# SCH_usb-eneko_2025-04-03.net
KiCad netlist of a schematic drawn in EasyEDA
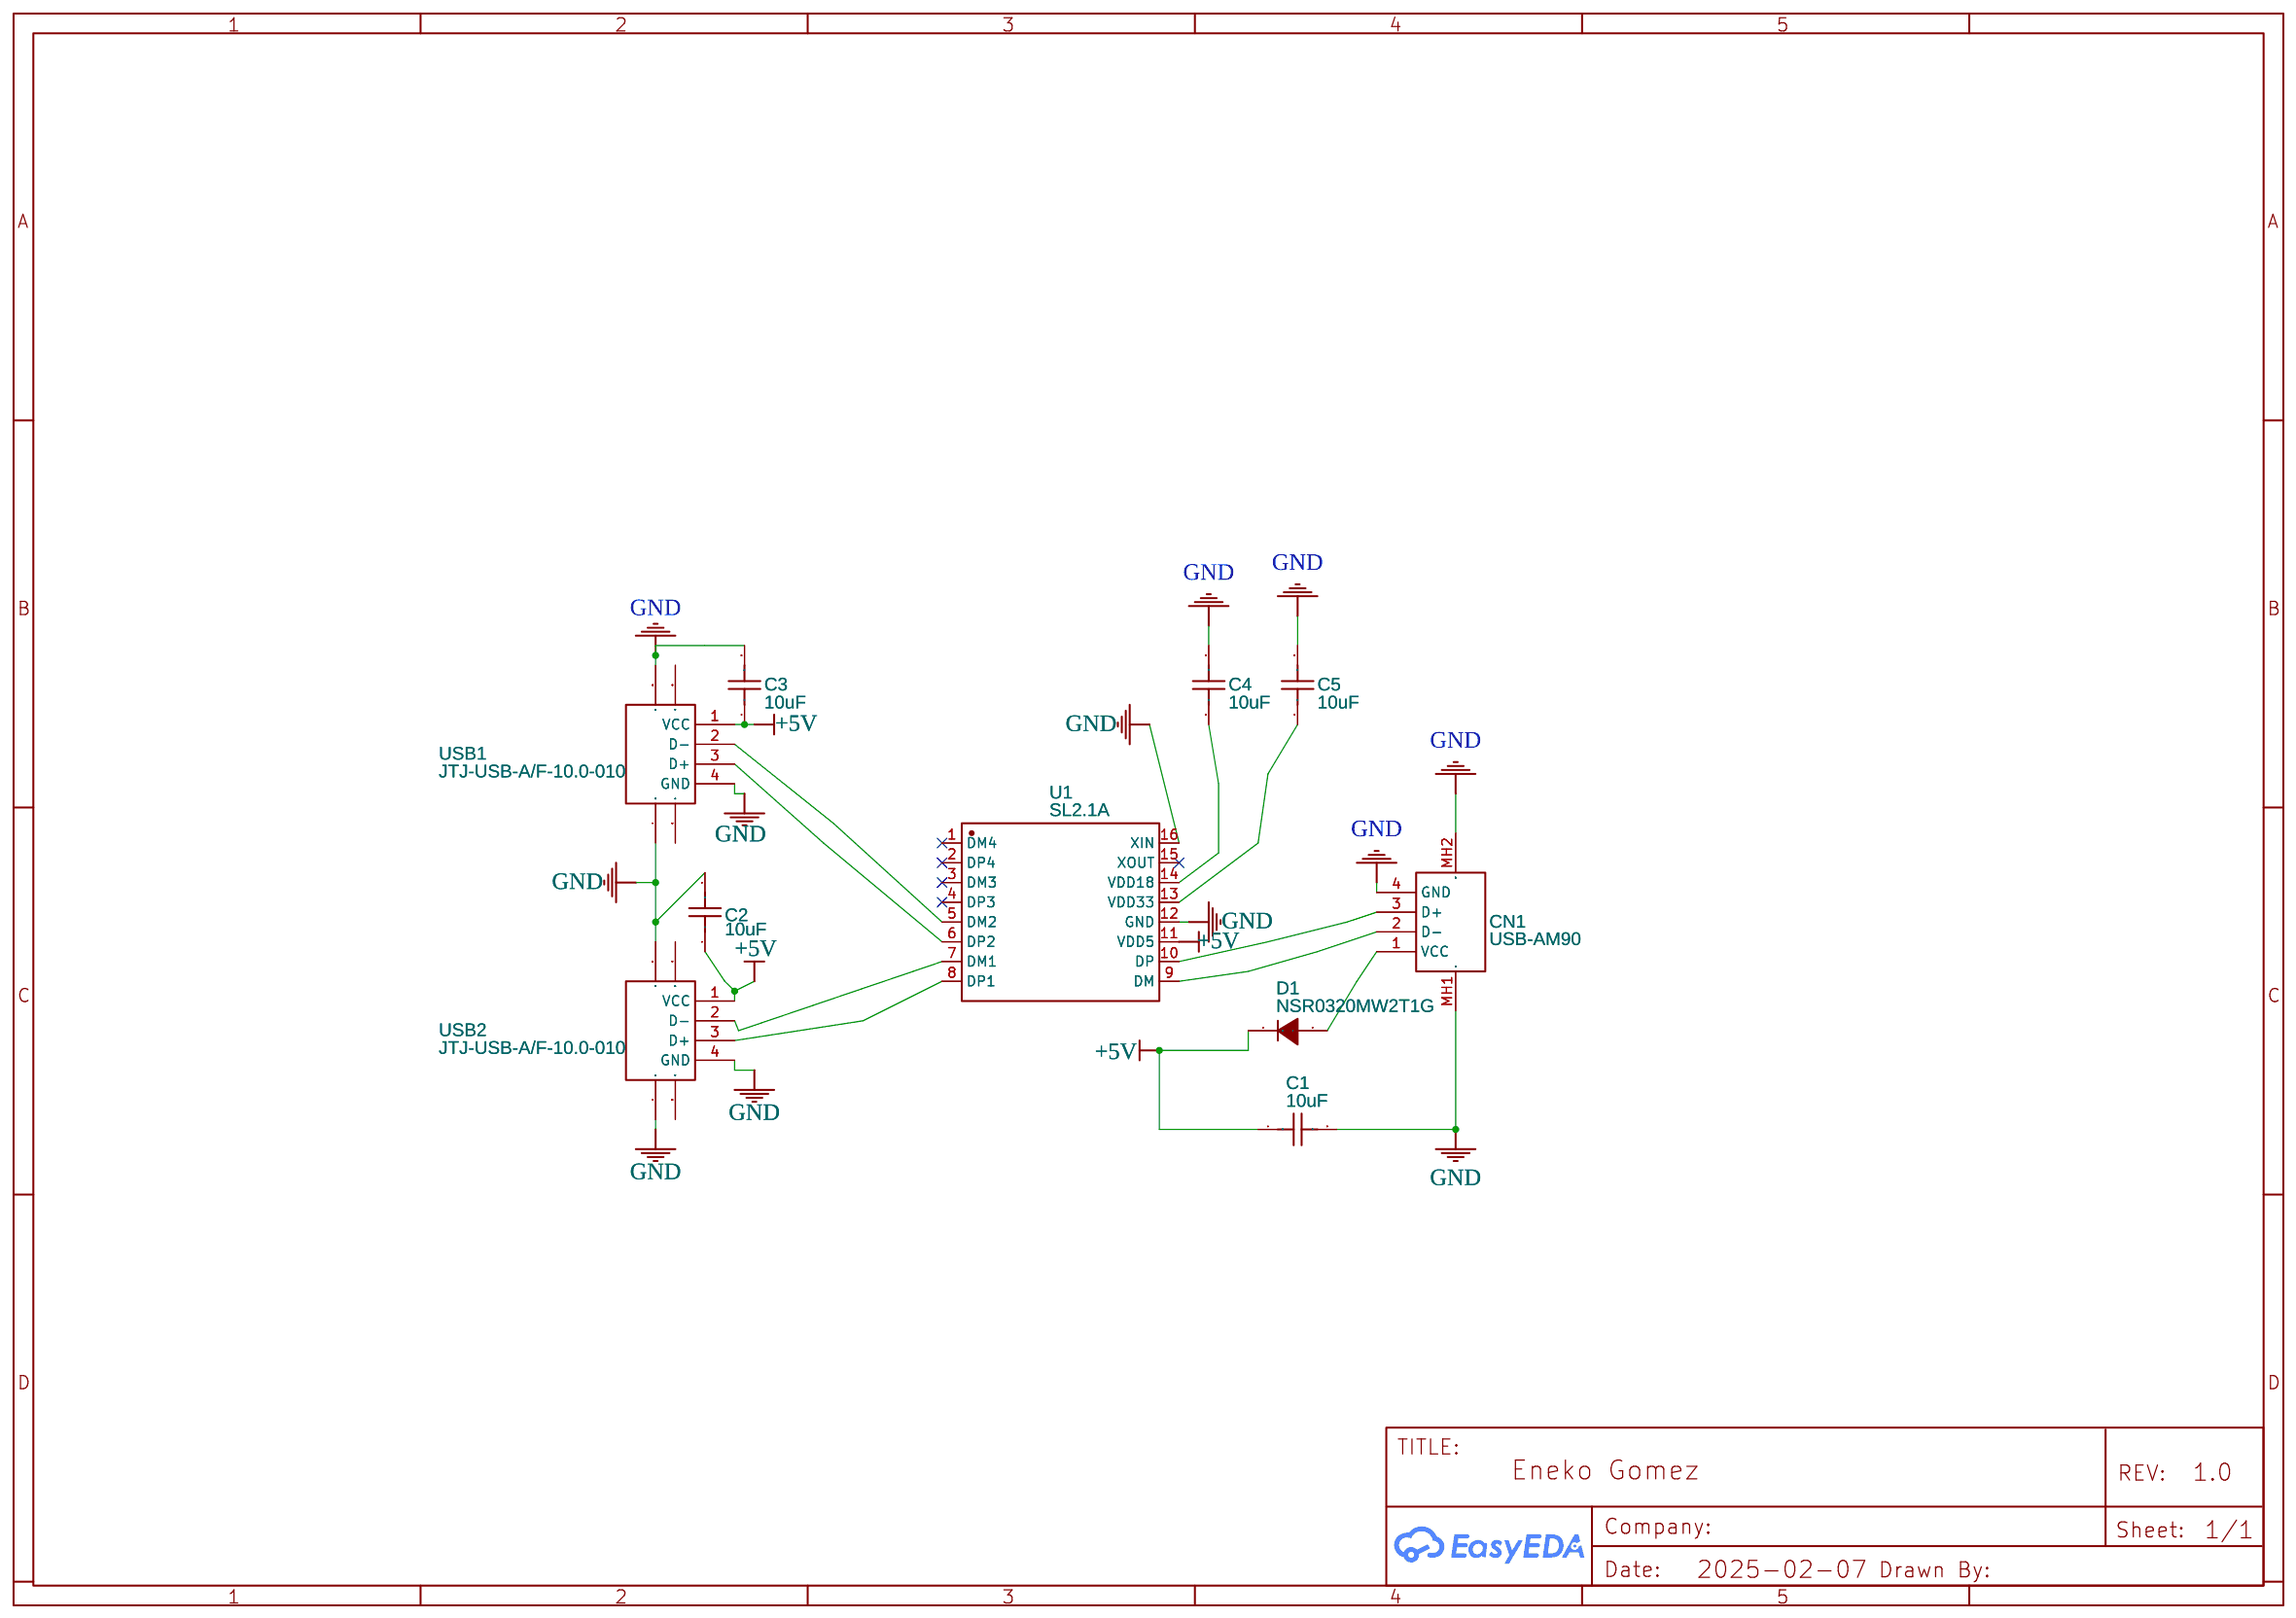
[diagram p0: schematic sheet]

(export (version "E")
  (design (tool "Eeschema 10.0.6"))
  (components
    (comp (ref "C1")
      (value "10uF")
      (fields
        (field (name "Manufacturer Part") "CL10A106KP8NNNC")
        (field (name "Manufacturer") "SAMSUNG(三星)")
      )
      (libsource (lib "") (part "CL10A106KP8NNNC_1"))
    )
    (comp (ref "C2")
      (value "10uF")
      (fields
        (field (name "Manufacturer Part") "CL10A106KP8NNNC")
        (field (name "Manufacturer") "SAMSUNG(三星)")
      )
      (libsource (lib "") (part "CL10A106KP8NNNC"))
    )
    (comp (ref "C3")
      (value "10uF")
      (fields
        (field (name "Manufacturer Part") "CL10A106KP8NNNC")
        (field (name "Manufacturer") "SAMSUNG(三星)")
      )
      (libsource (lib "") (part "CL10A106KP8NNNC"))
    )
    (comp (ref "C4")
      (value "10uF")
      (fields
        (field (name "Manufacturer Part") "CL10A106KP8NNNC")
        (field (name "Manufacturer") "SAMSUNG(三星)")
      )
      (libsource (lib "") (part "CL10A106KP8NNNC"))
    )
    (comp (ref "C5")
      (value "10uF")
      (fields
        (field (name "Manufacturer Part") "CL10A106KP8NNNC")
        (field (name "Manufacturer") "SAMSUNG(三星)")
      )
      (libsource (lib "") (part "CL10A106KP8NNNC"))
    )
    (comp (ref "CN1")
      (value "USB-AM90")
      (fields (field (name "Manufacturer") "ValuePro"))
      (libsource (lib "") (part "USB-AM90"))
    )
    (comp (ref "D1")
      (value "NSR0320MW2T1G")
      (fields (field (name "Manufacturer") "onsemi(安森美)"))
      (libsource (lib "") (part "NSR0320MW2T1G"))
    )
    (comp (ref "U1")
      (value "SL2.1A")
      (fields (field (name "Manufacturer") "CoreChips(和芯润德)"))
      (libsource (lib "") (part "SL2.1A"))
    )
    (comp (ref "USB1")
      (value "JTJ-USB-A/F-10.0-010")
      (fields (field (name "Manufacturer Part") "908-371A1011D10100") (field (name "Manufacturer") "精拓金"))
      (libsource (lib "") (part "JTJ-USB-A/F-10.0-010"))
    )
    (comp (ref "USB2")
      (value "JTJ-USB-A/F-10.0-010")
      (fields (field (name "Manufacturer Part") "908-371A1011D10100") (field (name "Manufacturer") "精拓金"))
      (libsource (lib "") (part "JTJ-USB-A/F-10.0-010"))
    )
  )
  (nets
    (net (code "1") (name "+5V") (class "Default")
      (node (ref "C1") (pin "1") (pinfunction "1_1") (pintype "unspecified"))
      (node (ref "C2") (pin "1") (pinfunction "1_1") (pintype "unspecified"))
      (node (ref "C3") (pin "1") (pinfunction "1_1") (pintype "unspecified"))
      (node (ref "D1") (pin "1") (pinfunction "C_1") (pintype "unspecified"))
      (node (ref "U1") (pin "11") (pinfunction "VDD5_11") (pintype "unspecified"))
      (node (ref "USB1") (pin "1") (pinfunction "VCC_1") (pintype "input"))
      (node (ref "USB2") (pin "1") (pinfunction "VCC_1") (pintype "input"))
    )
    (net (code "2") (name "GND") (class "Default")
      (node (ref "C1") (pin "2") (pinfunction "2_2") (pintype "unspecified"))
      (node (ref "C2") (pin "2") (pinfunction "2_2") (pintype "unspecified"))
      (node (ref "C3") (pin "2") (pinfunction "2_2") (pintype "unspecified"))
      (node (ref "C4") (pin "2") (pinfunction "2_2") (pintype "unspecified"))
      (node (ref "C5") (pin "2") (pinfunction "2_2") (pintype "unspecified"))
      (node (ref "CN1") (pin "4") (pinfunction "GND_4") (pintype "input"))
      (node (ref "CN1") (pin "MH1") (pinfunction "MH1_MH1") (pintype "unspecified"))
      (node (ref "CN1") (pin "MH2") (pinfunction "MH2_MH2") (pintype "unspecified"))
      (node (ref "U1") (pin "12") (pinfunction "GND_12") (pintype "unspecified"))
      (node (ref "U1") (pin "16") (pinfunction "XIN_16") (pintype "unspecified"))
      (node (ref "USB1") (pin "4") (pinfunction "GND_4") (pintype "input"))
      (node (ref "USB1") (pin "6") (pinfunction "0_6") (pintype "unspecified"))
      (node (ref "USB1") (pin "7") (pinfunction "0_7") (pintype "unspecified"))
      (node (ref "USB2") (pin "4") (pinfunction "GND_4") (pintype "input"))
      (node (ref "USB2") (pin "6") (pinfunction "0_6") (pintype "unspecified"))
      (node (ref "USB2") (pin "7") (pinfunction "0_7") (pintype "unspecified"))
    )
    (net (code "3") (name "Net-(CN1-D+)") (class "Default")
      (node (ref "CN1") (pin "3") (pinfunction "D+_3") (pintype "input"))
      (node (ref "U1") (pin "10") (pinfunction "DP_10") (pintype "unspecified"))
    )
    (net (code "4") (name "Net-(CN1-D-)") (class "Default")
      (node (ref "CN1") (pin "2") (pinfunction "D-_2") (pintype "input"))
      (node (ref "U1") (pin "9") (pinfunction "DM_9") (pintype "unspecified"))
    )
    (net (code "5") (name "Net-(CN1-VCC)") (class "Default")
      (node (ref "CN1") (pin "1") (pinfunction "VCC_1") (pintype "input"))
      (node (ref "D1") (pin "2") (pinfunction "A_2") (pintype "unspecified"))
    )
    (net (code "6") (name "Net-(U1-DM1)") (class "Default")
      (node (ref "U1") (pin "7") (pinfunction "DM1_7") (pintype "unspecified"))
      (node (ref "USB2") (pin "2") (pinfunction "D-_2") (pintype "input"))
    )
    (net (code "7") (name "Net-(U1-DM2)") (class "Default")
      (node (ref "U1") (pin "5") (pinfunction "DM2_5") (pintype "unspecified"))
      (node (ref "USB1") (pin "2") (pinfunction "D-_2") (pintype "input"))
    )
    (net (code "8") (name "Net-(U1-DP1)") (class "Default")
      (node (ref "U1") (pin "8") (pinfunction "DP1_8") (pintype "unspecified"))
      (node (ref "USB2") (pin "3") (pinfunction "D+_3") (pintype "input"))
    )
    (net (code "9") (name "Net-(U1-DP2)") (class "Default")
      (node (ref "U1") (pin "6") (pinfunction "DP2_6") (pintype "unspecified"))
      (node (ref "USB1") (pin "3") (pinfunction "D+_3") (pintype "input"))
    )
    (net (code "10") (name "Net-(U1-VDD18)") (class "Default")
      (node (ref "C4") (pin "1") (pinfunction "1_1") (pintype "unspecified"))
      (node (ref "U1") (pin "14") (pinfunction "VDD18_14") (pintype "unspecified"))
    )
    (net (code "11") (name "Net-(U1-VDD33)") (class "Default")
      (node (ref "C5") (pin "1") (pinfunction "1_1") (pintype "unspecified"))
      (node (ref "U1") (pin "13") (pinfunction "VDD33_13") (pintype "unspecified"))
    )
    (net (code "12") (name "unconnected-(U1-DM3-Pad3)") (class "Default")
      (node (ref "U1") (pin "3") (pinfunction "DM3_3") (pintype "unspecified+no_connect"))
    )
    (net (code "13") (name "unconnected-(U1-DM4-Pad1)") (class "Default")
      (node (ref "U1") (pin "1") (pinfunction "DM4_1") (pintype "unspecified+no_connect"))
    )
    (net (code "14") (name "unconnected-(U1-DP3-Pad4)") (class "Default")
      (node (ref "U1") (pin "4") (pinfunction "DP3_4") (pintype "unspecified+no_connect"))
    )
    (net (code "15") (name "unconnected-(U1-DP4-Pad2)") (class "Default")
      (node (ref "U1") (pin "2") (pinfunction "DP4_2") (pintype "unspecified+no_connect"))
    )
    (net (code "16") (name "unconnected-(U1-XOUT-Pad15)") (class "Default")
      (node (ref "U1") (pin "15") (pinfunction "XOUT_15") (pintype "unspecified+no_connect"))
    )
    (net (code "17") (name "unconnected-(USB1-0-Pad5)") (class "Default")
      (node (ref "USB1") (pin "5") (pinfunction "0_5") (pintype "unspecified"))
    )
    (net (code "18") (name "unconnected-(USB1-0-Pad8)") (class "Default")
      (node (ref "USB1") (pin "8") (pinfunction "0_8") (pintype "unspecified"))
    )
    (net (code "19") (name "unconnected-(USB2-0-Pad5)") (class "Default")
      (node (ref "USB2") (pin "5") (pinfunction "0_5") (pintype "unspecified"))
    )
    (net (code "20") (name "unconnected-(USB2-0-Pad8)") (class "Default")
      (node (ref "USB2") (pin "8") (pinfunction "0_8") (pintype "unspecified"))
    )
  )
)
